# Vobla.net
KiCad netlist of a schematic drawn in Altium Designer
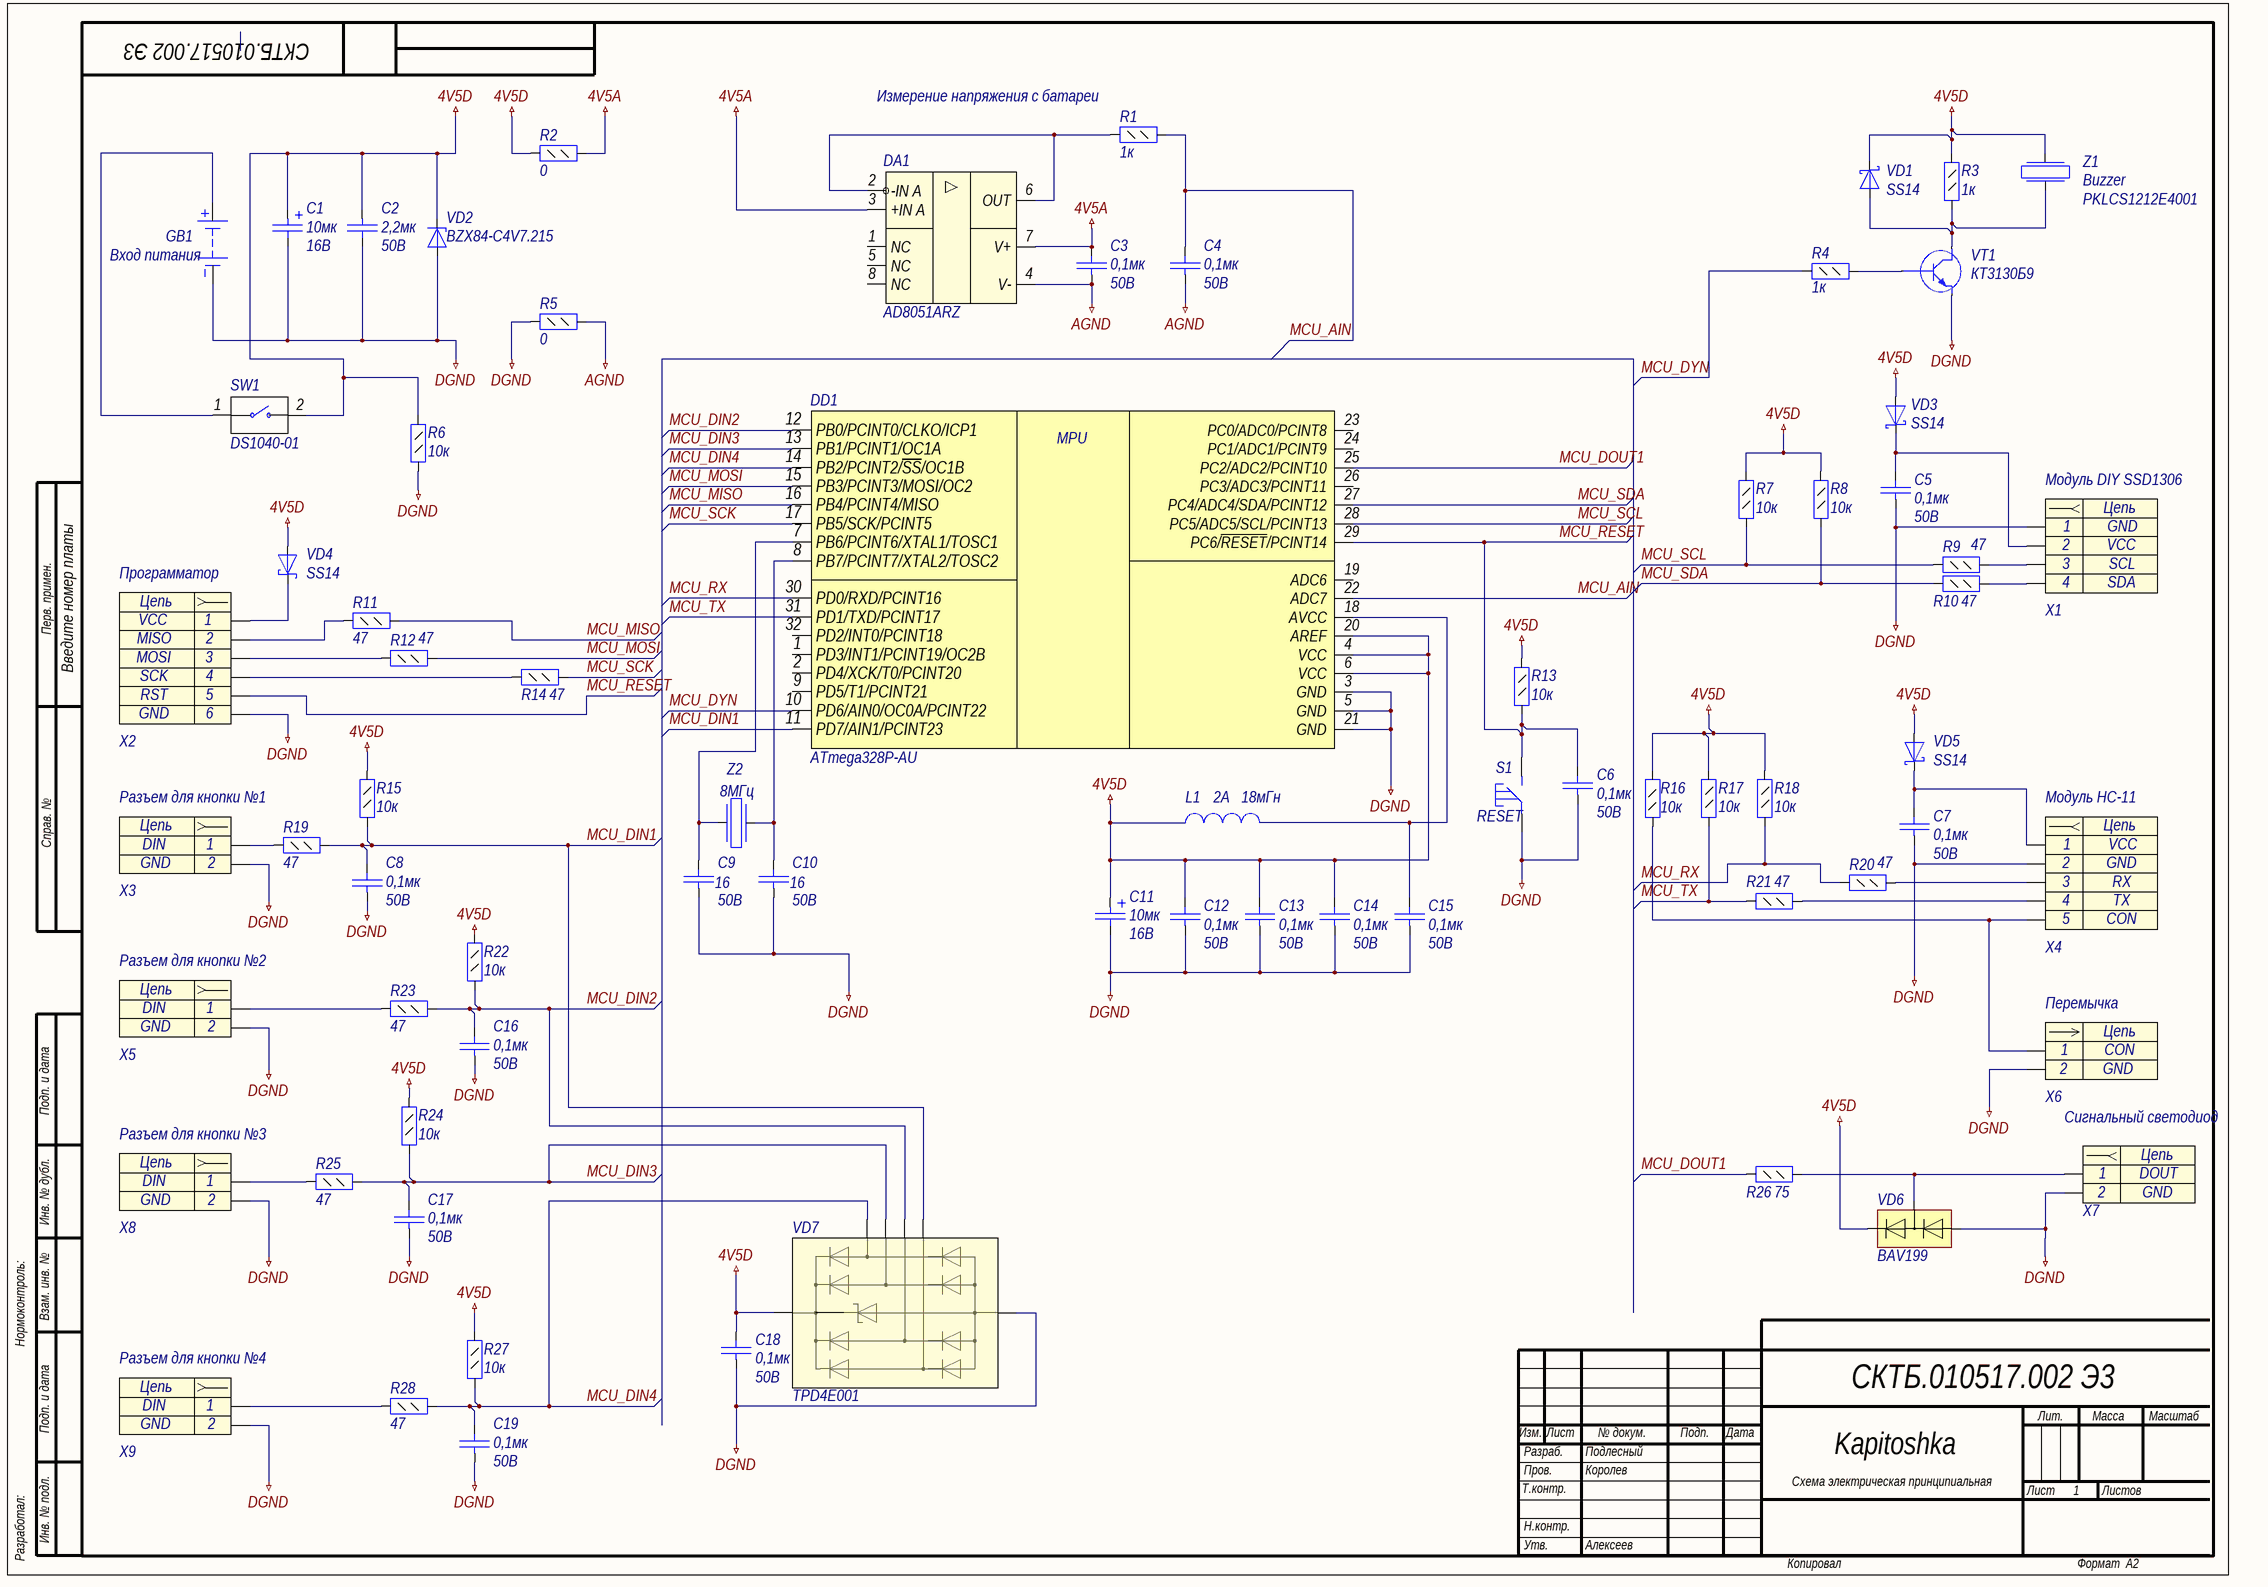
[diagram p0: Vobla.SchDoc]

(export (version "E")
  (design (tool "Eeschema 10.0.6"))
  (components
    (comp (ref "C1")
      (value "10мк")
      (footprint "Vobla:C1206")
      (description "Конденсатор полярный")
      (fields (field (name "VOLTAGE") "16В"))
      (libsource (lib "Vobla") (part "Capacitor_pol"))
    )
    (comp (ref "C2")
      (value "2,2мк")
      (footprint "Vobla:C0603")
      (description "Конденсатор")
      (fields (field (name "VOLTAGE") "50В"))
      (libsource (lib "Vobla") (part "Capacitor"))
    )
    (comp (ref "C3")
      (value "0,1мк")
      (footprint "Vobla:C0603")
      (description "Конденсатор")
      (fields (field (name "VOLTAGE") "50В"))
      (libsource (lib "Vobla") (part "Capacitor"))
    )
    (comp (ref "C4")
      (value "0,1мк")
      (footprint "Vobla:C0603")
      (description "Конденсатор")
      (fields (field (name "VOLTAGE") "50В"))
      (libsource (lib "Vobla") (part "Capacitor"))
    )
    (comp (ref "C5")
      (value "0,1мк")
      (footprint "Vobla:C0603")
      (description "Конденсатор")
      (fields (field (name "VOLTAGE") "50В"))
      (libsource (lib "Vobla") (part "Capacitor"))
    )
    (comp (ref "C6")
      (value "0,1мк")
      (footprint "Vobla:C0603")
      (description "Конденсатор")
      (fields (field (name "VOLTAGE") "50В"))
      (libsource (lib "Vobla") (part "Capacitor"))
    )
    (comp (ref "C7")
      (value "0,1мк")
      (footprint "Vobla:C0603")
      (description "Конденсатор")
      (fields (field (name "VOLTAGE") "50В"))
      (libsource (lib "Vobla") (part "Capacitor"))
    )
    (comp (ref "C8")
      (value "0,1мк")
      (footprint "Vobla:C0603")
      (description "Конденсатор")
      (fields (field (name "VOLTAGE") "50В"))
      (libsource (lib "Vobla") (part "Capacitor"))
    )
    (comp (ref "C9")
      (value "16")
      (footprint "Vobla:C0603")
      (description "Конденсатор")
      (fields (field (name "VOLTAGE") "50В"))
      (libsource (lib "Vobla") (part "Capacitor"))
    )
    (comp (ref "C10")
      (value "16")
      (footprint "Vobla:C0603")
      (description "Конденсатор")
      (fields (field (name "VOLTAGE") "50В"))
      (libsource (lib "Vobla") (part "Capacitor"))
    )
    (comp (ref "C11")
      (value "10мк")
      (footprint "Vobla:C1206")
      (description "Конденсатор полярный")
      (fields (field (name "VOLTAGE") "16В"))
      (libsource (lib "Vobla") (part "Capacitor_pol"))
    )
    (comp (ref "C12")
      (value "0,1мк")
      (footprint "Vobla:C0603")
      (description "Конденсатор")
      (fields (field (name "VOLTAGE") "50В"))
      (libsource (lib "Vobla") (part "Capacitor"))
    )
    (comp (ref "C13")
      (value "0,1мк")
      (footprint "Vobla:C0603")
      (description "Конденсатор")
      (fields (field (name "VOLTAGE") "50В"))
      (libsource (lib "Vobla") (part "Capacitor"))
    )
    (comp (ref "C14")
      (value "0,1мк")
      (footprint "Vobla:C0603")
      (description "Конденсатор")
      (fields (field (name "VOLTAGE") "50В"))
      (libsource (lib "Vobla") (part "Capacitor"))
    )
    (comp (ref "C15")
      (value "0,1мк")
      (footprint "Vobla:C0603")
      (description "Конденсатор")
      (fields (field (name "VOLTAGE") "50В"))
      (libsource (lib "Vobla") (part "Capacitor"))
    )
    (comp (ref "C16")
      (value "0,1мк")
      (footprint "Vobla:C0603")
      (description "Конденсатор")
      (fields (field (name "VOLTAGE") "50В"))
      (libsource (lib "Vobla") (part "Capacitor"))
    )
    (comp (ref "C17")
      (value "0,1мк")
      (footprint "Vobla:C0603")
      (description "Конденсатор")
      (fields (field (name "VOLTAGE") "50В"))
      (libsource (lib "Vobla") (part "Capacitor"))
    )
    (comp (ref "C18")
      (value "0,1мк")
      (footprint "Vobla:C0603")
      (description "Конденсатор")
      (fields (field (name "VOLTAGE") "50В"))
      (libsource (lib "Vobla") (part "Capacitor"))
    )
    (comp (ref "C19")
      (value "0,1мк")
      (footprint "Vobla:C0603")
      (description "Конденсатор")
      (fields (field (name "VOLTAGE") "50В"))
      (libsource (lib "Vobla") (part "Capacitor"))
    )
    (comp (ref "DA1")
      (value "AD8051ARZ")
      (footprint "Vobla:SO8_H")
      (description "ОУ")
      (fields (field (name "NAME") "AD8051ARZ"))
      (libsource (lib "Vobla") (part "AD8051ARZ"))
    )
    (comp (ref "DD1")
      (value "ATmega328P-AU")
      (footprint "Vobla:TQFP-32")
      (description "Микроконтроллер 64-pin")
      (fields (field (name "NAME") "ATmega328P-AU"))
      (libsource (lib "Vobla") (part "ATmega328P-AU"))
    )
    (comp (ref "GB1")
      (value "Вход питания")
      (footprint "Vobla:KLS5-818-С")
      (libsource (lib "Vobla") (part "Battery compartment"))
    )
    (comp (ref "L1")
      (value "18мГн")
      (footprint "Vobla:L0603_H")
      (description "Катушка индуктивности")
      (fields (field (name "IMAX") "2А"))
      (libsource (lib "Vobla") (part "Inductor"))
    )
    (comp (ref "R1")
      (value "1к")
      (footprint "Vobla:R0603")
      (description "Резистор")
      (libsource (lib "Vobla") (part "Resistor_0,125Вт"))
    )
    (comp (ref "R2")
      (value "0")
      (footprint "Vobla:R0603")
      (description "Резистор")
      (libsource (lib "Vobla") (part "Resistor_0,125Вт"))
    )
    (comp (ref "R3")
      (value "1к")
      (footprint "Vobla:R0603")
      (description "Резистор")
      (libsource (lib "") (part "Resistor_0,125Вт_1"))
    )
    (comp (ref "R4")
      (value "1к")
      (footprint "Vobla:R0603")
      (description "Резистор")
      (libsource (lib "Vobla") (part "Resistor_0,125Вт"))
    )
    (comp (ref "R5")
      (value "0")
      (footprint "Vobla:R0603")
      (description "Резистор")
      (libsource (lib "Vobla") (part "Resistor_0,125Вт"))
    )
    (comp (ref "R6")
      (value "10к")
      (footprint "Vobla:R0603")
      (description "Резистор")
      (libsource (lib "") (part "Resistor_0,125Вт_1"))
    )
    (comp (ref "R7")
      (value "10к")
      (footprint "Vobla:R0603")
      (description "Резистор")
      (libsource (lib "") (part "Resistor_0,125Вт_1"))
    )
    (comp (ref "R8")
      (value "10к")
      (footprint "Vobla:R0603")
      (description "Резистор")
      (libsource (lib "") (part "Resistor_0,125Вт_1"))
    )
    (comp (ref "R9")
      (value "47")
      (footprint "Vobla:R0603")
      (description "Резистор")
      (libsource (lib "Vobla") (part "Resistor_0,125Вт"))
    )
    (comp (ref "R10")
      (value "47")
      (footprint "Vobla:R0603")
      (description "Резистор")
      (libsource (lib "Vobla") (part "Resistor_0,125Вт"))
    )
    (comp (ref "R11")
      (value "47")
      (footprint "Vobla:R0603")
      (description "Резистор")
      (libsource (lib "Vobla") (part "Resistor_0,125Вт"))
    )
    (comp (ref "R12")
      (value "47")
      (footprint "Vobla:R0603")
      (description "Резистор")
      (libsource (lib "Vobla") (part "Resistor_0,125Вт"))
    )
    (comp (ref "R13")
      (value "10к")
      (footprint "Vobla:R0603")
      (description "Резистор")
      (libsource (lib "") (part "Resistor_0,125Вт_1"))
    )
    (comp (ref "R14")
      (value "47")
      (footprint "Vobla:R0603")
      (description "Резистор")
      (libsource (lib "Vobla") (part "Resistor_0,125Вт"))
    )
    (comp (ref "R15")
      (value "10к")
      (footprint "Vobla:R0603")
      (description "Резистор")
      (libsource (lib "") (part "Resistor_0,125Вт_1"))
    )
    (comp (ref "R16")
      (value "10к")
      (footprint "Vobla:R0603")
      (description "Резистор")
      (libsource (lib "") (part "Resistor_0,125Вт_2"))
    )
    (comp (ref "R17")
      (value "10к")
      (footprint "Vobla:R0603")
      (description "Резистор")
      (libsource (lib "") (part "Resistor_0,125Вт_1"))
    )
    (comp (ref "R18")
      (value "10к")
      (footprint "Vobla:R0603")
      (description "Резистор")
      (libsource (lib "") (part "Resistor_0,125Вт_1"))
    )
    (comp (ref "R19")
      (value "47")
      (footprint "Vobla:R0603")
      (description "Резистор")
      (libsource (lib "Vobla") (part "Resistor_0,125Вт"))
    )
    (comp (ref "R20")
      (value "47")
      (footprint "Vobla:R0603")
      (description "Резистор")
      (libsource (lib "Vobla") (part "Resistor_0,125Вт"))
    )
    (comp (ref "R21")
      (value "47")
      (footprint "Vobla:R0603")
      (description "Резистор")
      (libsource (lib "Vobla") (part "Resistor_0,125Вт"))
    )
    (comp (ref "R22")
      (value "10к")
      (footprint "Vobla:R0603")
      (description "Резистор")
      (libsource (lib "") (part "Resistor_0,125Вт_1"))
    )
    (comp (ref "R23")
      (value "47")
      (footprint "Vobla:R0603")
      (description "Резистор")
      (libsource (lib "Vobla") (part "Resistor_0,125Вт"))
    )
    (comp (ref "R24")
      (value "10к")
      (footprint "Vobla:R0603")
      (description "Резистор")
      (libsource (lib "") (part "Resistor_0,125Вт_1"))
    )
    (comp (ref "R25")
      (value "47")
      (footprint "Vobla:R0603")
      (description "Резистор")
      (libsource (lib "Vobla") (part "Resistor_0,125Вт"))
    )
    (comp (ref "R26")
      (value "75")
      (footprint "Vobla:R0603")
      (description "Резистор")
      (libsource (lib "Vobla") (part "Resistor_0,125Вт"))
    )
    (comp (ref "R27")
      (value "10к")
      (footprint "Vobla:R0603")
      (description "Резистор")
      (libsource (lib "") (part "Resistor_0,125Вт_1"))
    )
    (comp (ref "R28")
      (value "47")
      (footprint "Vobla:R0603")
      (description "Резистор")
      (libsource (lib "Vobla") (part "Resistor_0,125Вт"))
    )
    (comp (ref "S1")
      (value "RESET")
      (footprint "Vobla:DTSM 32")
      (description "Кнопка")
      (fields (field (name "NAME") "RESET"))
      (libsource (lib "Vobla") (part "Button_SMD"))
    )
    (comp (ref "SW1")
      (value "DS1040-01")
      (footprint "Vobla:DIP1")
      (description "DIP переключатель")
      (libsource (lib "Vobla") (part "DS1040-01"))
    )
    (comp (ref "VD1")
      (value "SS14")
      (footprint "Vobla:SMA")
      (description "Диод Шоттки")
      (libsource (lib "Vobla") (part "DiodeSchottky"))
    )
    (comp (ref "VD2")
      (value "BZX84-C4V7.215")
      (footprint "Vobla:SOT23-2_H")
      (description "Стабилитрон")
      (libsource (lib "Vobla") (part "DiodeZener"))
    )
    (comp (ref "VD3")
      (value "SS14")
      (footprint "Vobla:SMA")
      (description "Диод Шоттки")
      (libsource (lib "Vobla") (part "DiodeSchottky"))
    )
    (comp (ref "VD4")
      (value "SS14")
      (footprint "Vobla:SMA")
      (description "Диод Шоттки")
      (libsource (lib "Vobla") (part "DiodeSchottky"))
    )
    (comp (ref "VD5")
      (value "SS14")
      (footprint "Vobla:SMA")
      (description "Диод Шоттки")
      (libsource (lib "Vobla") (part "DiodeSchottky"))
    )
    (comp (ref "VD6")
      (value "BAV199")
      (footprint "Vobla:SOT23-3")
      (description "Диодная сборка")
      (libsource (lib "Vobla") (part "BAV199"))
    )
    (comp (ref "VD7")
      (value "TPD4E001")
      (footprint "Vobla:SOT23-6")
      (description "Диодная сборка")
      (fields (field (name "MANUFACTURER") "Texas Instruments"))
      (libsource (lib "Vobla") (part "TPD4E001"))
    )
    (comp (ref "VT1")
      (value "КТ3130Б9")
      (footprint "Vobla:SOT23-3")
      (fields (field (name "POWER") "0.1Вт"))
      (libsource (lib "Vobla") (part "КТ3130Б9"))
    )
    (comp (ref "X1")
      (value "Модуль DIY SSD1306")
      (footprint "Vobla:4HOLE_WIRE")
      (description "Разъем - 4 конт. розетка")
      (libsource (lib "Vobla") (part "Header_4_sct"))
    )
    (comp (ref "X2")
      (value "Программатор")
      (footprint "Vobla:6HOLE_WIRE")
      (description "Разъем - 5 конт. розетка")
      (libsource (lib "Vobla") (part "Header_6_sct"))
    )
    (comp (ref "X3")
      (value "Разъем для кнопки №1")
      (footprint "Vobla:2HOLE_Button")
      (description "Разъем - 2 конт. розетка")
      (libsource (lib "Vobla") (part "Header_2_sct"))
    )
    (comp (ref "X4")
      (value "Модуль HC-11")
      (footprint "Vobla:5HOLE_WIRE")
      (description "Разъем - 4 конт. розетка")
      (libsource (lib "Vobla") (part "Header_5_sct"))
    )
    (comp (ref "X5")
      (value "Разъем для кнопки №2")
      (footprint "Vobla:2HOLE_Button")
      (description "Разъем - 2 конт. розетка")
      (libsource (lib "Vobla") (part "Header_2_sct"))
    )
    (comp (ref "X6")
      (value "Перемычка")
      (footprint "Vobla:PLS2-2")
      (description "Разъем - 2 конт. вилка")
      (libsource (lib "Vobla") (part "Header_2_plg"))
    )
    (comp (ref "X7")
      (value "Сигнальный светодиод")
      (footprint "Vobla:2HOLE_Led")
      (description "Разъем - 2 конт. розетка")
      (libsource (lib "") (part "Header_2_sct_1"))
    )
    (comp (ref "X8")
      (value "Разъем для кнопки №3")
      (footprint "Vobla:2HOLE_Button")
      (description "Разъем - 2 конт. розетка")
      (libsource (lib "Vobla") (part "Header_2_sct"))
    )
    (comp (ref "X9")
      (value "Разъем для кнопки №4")
      (footprint "Vobla:2HOLE_Button")
      (description "Разъем - 2 конт. розетка")
      (libsource (lib "Vobla") (part "Header_2_sct"))
    )
    (comp (ref "Z1")
      (value "PKLCS1212E4001")
      (footprint "Vobla:Piezoelectric Sounder")
      (description "Пьезоизлучатель звуковой")
      (fields (field (name "ALTIUM_VALUE") "Buzzer"))
      (libsource (lib "Vobla") (part "Buzzer"))
    )
    (comp (ref "Z2")
      (value "8МГц")
      (footprint "Vobla:QSMD3.2x5")
      (description "Кварцевый резонатор")
      (libsource (lib "Vobla") (part "Crystal"))
    )
  )
  (nets
    (net (code "1") (name "/MCU_AIN") (class "Default")
      (node (ref "C4") (pin "2") (pinfunction "2_2") (pintype "passive"))
      (node (ref "DD1") (pin "22") (pinfunction "ADC7_22") (pintype "passive"))
      (node (ref "R1") (pin "2") (pinfunction "5_2") (pintype "passive"))
    )
    (net (code "2") (name "/MCU_DIN1") (class "Default")
      (node (ref "C8") (pin "2") (pinfunction "2_2") (pintype "passive"))
      (node (ref "DD1") (pin "11") (pinfunction "PD7/AIN1/PCINT23_11") (pintype "passive"))
      (node (ref "R15") (pin "2") (pinfunction "5_2") (pintype "passive"))
      (node (ref "R19") (pin "2") (pinfunction "5_2") (pintype "passive"))
      (node (ref "VD7") (pin "6") (pinfunction "IO4_6") (pintype "passive"))
    )
    (net (code "3") (name "/MCU_DIN2") (class "Default")
      (node (ref "C16") (pin "2") (pinfunction "2_2") (pintype "passive"))
      (node (ref "DD1") (pin "12") (pinfunction "PB0/PCINT0/CLKO/ICP1_12") (pintype "passive"))
      (node (ref "R22") (pin "2") (pinfunction "5_2") (pintype "passive"))
      (node (ref "R23") (pin "2") (pinfunction "5_2") (pintype "passive"))
      (node (ref "VD7") (pin "4") (pinfunction "IO3_4") (pintype "passive"))
    )
    (net (code "4") (name "/MCU_DIN3") (class "Default")
      (node (ref "C17") (pin "2") (pinfunction "2_2") (pintype "passive"))
      (node (ref "DD1") (pin "13") (pinfunction "PB1/PCINT1/OC1A_13") (pintype "passive"))
      (node (ref "R24") (pin "2") (pinfunction "5_2") (pintype "passive"))
      (node (ref "R25") (pin "2") (pinfunction "5_2") (pintype "passive"))
      (node (ref "VD7") (pin "3") (pinfunction "IO2_3") (pintype "passive"))
    )
    (net (code "5") (name "/MCU_DIN4") (class "Default")
      (node (ref "C19") (pin "2") (pinfunction "2_2") (pintype "passive"))
      (node (ref "DD1") (pin "14") (pinfunction "PB2/PCINT2/~{SS}/OC1B_14") (pintype "passive"))
      (node (ref "R27") (pin "2") (pinfunction "5_2") (pintype "passive"))
      (node (ref "R28") (pin "2") (pinfunction "5_2") (pintype "passive"))
      (node (ref "VD7") (pin "1") (pinfunction "IO1_1") (pintype "passive"))
    )
    (net (code "6") (name "/MCU_DOUT1") (class "Default")
      (node (ref "DD1") (pin "25") (pinfunction "PC2/ADC2/PCINT10_25") (pintype "passive"))
      (node (ref "R26") (pin "1") (pinfunction "1_1") (pintype "passive"))
    )
    (net (code "7") (name "/MCU_DYN") (class "Default")
      (node (ref "DD1") (pin "10") (pinfunction "PD6/AIN0/OC0A/PCINT22_10") (pintype "passive"))
      (node (ref "R4") (pin "1") (pinfunction "1_1") (pintype "passive"))
    )
    (net (code "8") (name "/MCU_MISO") (class "Default")
      (node (ref "DD1") (pin "16") (pinfunction "PB4/PCINT4/MISO_16") (pintype "passive"))
      (node (ref "R11") (pin "2") (pinfunction "5_2") (pintype "passive"))
    )
    (net (code "9") (name "/MCU_MOSI") (class "Default")
      (node (ref "DD1") (pin "15") (pinfunction "PB3/PCINT3/MOSI/OC2_15") (pintype "passive"))
      (node (ref "R12") (pin "2") (pinfunction "5_2") (pintype "passive"))
    )
    (net (code "10") (name "/MCU_RESET") (class "Default")
      (node (ref "C6") (pin "2") (pinfunction "2_2") (pintype "passive"))
      (node (ref "DD1") (pin "29") (pinfunction "PC6/~{RESET}/PCINT14_29") (pintype "passive"))
      (node (ref "R13") (pin "2") (pinfunction "5_2") (pintype "passive"))
      (node (ref "S1") (pin "3") (pinfunction "3_3") (pintype "passive"))
      (node (ref "X2") (pin "5") (pinfunction "5_5") (pintype "passive"))
    )
    (net (code "11") (name "/MCU_RX") (class "Default")
      (node (ref "DD1") (pin "30") (pinfunction "PD0/RXD/PCINT16_30") (pintype "passive"))
      (node (ref "R18") (pin "2") (pinfunction "5_2") (pintype "passive"))
      (node (ref "R20") (pin "1") (pinfunction "1_1") (pintype "passive"))
    )
    (net (code "12") (name "/MCU_SCK") (class "Default")
      (node (ref "DD1") (pin "17") (pinfunction "PB5/SCK/PCINT5_17") (pintype "passive"))
      (node (ref "R14") (pin "2") (pinfunction "5_2") (pintype "passive"))
    )
    (net (code "13") (name "/MCU_SCL") (class "Default")
      (node (ref "DD1") (pin "28") (pinfunction "PC5/ADC5/SCL/PCINT13_28") (pintype "passive"))
      (node (ref "R7") (pin "2") (pinfunction "5_2") (pintype "passive"))
      (node (ref "R9") (pin "1") (pinfunction "1_1") (pintype "passive"))
    )
    (net (code "14") (name "/MCU_SDA") (class "Default")
      (node (ref "DD1") (pin "27") (pinfunction "PC4/ADC4/SDA/PCINT12_27") (pintype "passive"))
      (node (ref "R10") (pin "1") (pinfunction "1_1") (pintype "passive"))
      (node (ref "R8") (pin "2") (pinfunction "5_2") (pintype "passive"))
    )
    (net (code "15") (name "/MCU_TX") (class "Default")
      (node (ref "DD1") (pin "31") (pinfunction "PD1/TXD/PCINT17_31") (pintype "passive"))
      (node (ref "R17") (pin "2") (pinfunction "5_2") (pintype "passive"))
      (node (ref "R21") (pin "1") (pinfunction "1_1") (pintype "passive"))
    )
    (net (code "16") (name "4V5A") (class "Default")
      (node (ref "C3") (pin "2") (pinfunction "2_2") (pintype "passive"))
      (node (ref "DA1") (pin "3") (pinfunction "+IN_A_3") (pintype "passive"))
      (node (ref "DA1") (pin "7") (pinfunction "V+_7") (pintype "passive"))
      (node (ref "R2") (pin "2") (pinfunction "5_2") (pintype "passive"))
    )
    (net (code "17") (name "4V5D") (class "Default")
      (node (ref "C1") (pin "1") (pinfunction "1_1") (pintype "passive"))
      (node (ref "C11") (pin "1") (pinfunction "1_1") (pintype "passive"))
      (node (ref "C12") (pin "2") (pinfunction "2_2") (pintype "passive"))
      (node (ref "C13") (pin "2") (pinfunction "2_2") (pintype "passive"))
      (node (ref "C14") (pin "2") (pinfunction "2_2") (pintype "passive"))
      (node (ref "C18") (pin "2") (pinfunction "2_2") (pintype "passive"))
      (node (ref "C2") (pin "1") (pinfunction "1_1") (pintype "passive"))
      (node (ref "DD1") (pin "20") (pinfunction "AREF_20") (pintype "passive"))
      (node (ref "DD1") (pin "4") (pinfunction "VCC_4") (pintype "passive"))
      (node (ref "DD1") (pin "6") (pinfunction "VCC_6") (pintype "passive"))
      (node (ref "L1") (pin "1") (pinfunction "1_1") (pintype "passive"))
      (node (ref "R13") (pin "1") (pinfunction "1_1") (pintype "passive"))
      (node (ref "R15") (pin "1") (pinfunction "1_1") (pintype "passive"))
      (node (ref "R16") (pin "2") (pinfunction "5_2") (pintype "passive"))
      (node (ref "R17") (pin "1") (pinfunction "1_1") (pintype "passive"))
      (node (ref "R18") (pin "1") (pinfunction "1_1") (pintype "passive"))
      (node (ref "R2") (pin "1") (pinfunction "1_1") (pintype "passive"))
      (node (ref "R22") (pin "1") (pinfunction "1_1") (pintype "passive"))
      (node (ref "R24") (pin "1") (pinfunction "1_1") (pintype "passive"))
      (node (ref "R27") (pin "1") (pinfunction "1_1") (pintype "passive"))
      (node (ref "R3") (pin "1") (pinfunction "1_1") (pintype "passive"))
      (node (ref "R6") (pin "1") (pinfunction "1_1") (pintype "passive"))
      (node (ref "R7") (pin "1") (pinfunction "1_1") (pintype "passive"))
      (node (ref "R8") (pin "1") (pinfunction "1_1") (pintype "passive"))
      (node (ref "SW1") (pin "2") (pintype "passive"))
      (node (ref "VD1") (pin "1") (pinfunction "K_1") (pintype "passive"))
      (node (ref "VD2") (pin "1") (pinfunction "K_1") (pintype "passive"))
      (node (ref "VD3") (pin "2") (pinfunction "A_2") (pintype "passive"))
      (node (ref "VD4") (pin "2") (pinfunction "A_2") (pintype "passive"))
      (node (ref "VD5") (pin "2") (pinfunction "A_2") (pintype "passive"))
      (node (ref "VD6") (pin "1") (pintype "passive"))
      (node (ref "VD7") (pin "5") (pinfunction "VCC_5") (pintype "passive"))
      (node (ref "Z1") (pin "2") (pinfunction "2_2") (pintype "passive"))
    )
    (net (code "18") (name "AGND") (class "Default")
      (node (ref "C3") (pin "1") (pinfunction "1_1") (pintype "passive"))
      (node (ref "C4") (pin "1") (pinfunction "1_1") (pintype "passive"))
      (node (ref "DA1") (pin "4") (pinfunction "V-_4") (pintype "passive"))
      (node (ref "R5") (pin "2") (pinfunction "5_2") (pintype "passive"))
    )
    (net (code "19") (name "DGND") (class "Default")
      (node (ref "C1") (pin "2") (pinfunction "2_2") (pintype "passive"))
      (node (ref "C10") (pin "1") (pinfunction "1_1") (pintype "passive"))
      (node (ref "C11") (pin "2") (pinfunction "2_2") (pintype "passive"))
      (node (ref "C12") (pin "1") (pinfunction "1_1") (pintype "passive"))
      (node (ref "C13") (pin "1") (pinfunction "1_1") (pintype "passive"))
      (node (ref "C14") (pin "1") (pinfunction "1_1") (pintype "passive"))
      (node (ref "C15") (pin "1") (pinfunction "1_1") (pintype "passive"))
      (node (ref "C16") (pin "1") (pinfunction "1_1") (pintype "passive"))
      (node (ref "C17") (pin "1") (pinfunction "1_1") (pintype "passive"))
      (node (ref "C18") (pin "1") (pinfunction "1_1") (pintype "passive"))
      (node (ref "C19") (pin "1") (pinfunction "1_1") (pintype "passive"))
      (node (ref "C2") (pin "2") (pinfunction "2_2") (pintype "passive"))
      (node (ref "C5") (pin "1") (pinfunction "1_1") (pintype "passive"))
      (node (ref "C6") (pin "1") (pinfunction "1_1") (pintype "passive"))
      (node (ref "C7") (pin "1") (pinfunction "1_1") (pintype "passive"))
      (node (ref "C8") (pin "1") (pinfunction "1_1") (pintype "passive"))
      (node (ref "C9") (pin "1") (pinfunction "1_1") (pintype "passive"))
      (node (ref "DD1") (pin "21") (pinfunction "GND_21") (pintype "passive"))
      (node (ref "DD1") (pin "3") (pinfunction "GND_3") (pintype "passive"))
      (node (ref "DD1") (pin "5") (pinfunction "GND_5") (pintype "passive"))
      (node (ref "GB1") (pin "2") (pinfunction "2_2") (pintype "passive"))
      (node (ref "R5") (pin "1") (pinfunction "1_1") (pintype "passive"))
      (node (ref "R6") (pin "2") (pinfunction "5_2") (pintype "passive"))
      (node (ref "S1") (pin "1") (pinfunction "1_1") (pintype "passive"))
      (node (ref "VD2") (pin "2") (pinfunction "A_2") (pintype "passive"))
      (node (ref "VD6") (pin "2") (pintype "passive"))
      (node (ref "VD7") (pin "2") (pinfunction "GND_2") (pintype "passive"))
      (node (ref "VT1") (pin "2") (pinfunction "Emitter_2") (pintype "passive"))
      (node (ref "X1") (pin "1") (pinfunction "1_1") (pintype "passive"))
      (node (ref "X2") (pin "6") (pinfunction "6_6") (pintype "passive"))
      (node (ref "X3") (pin "2") (pinfunction "2_2") (pintype "passive"))
      (node (ref "X4") (pin "2") (pinfunction "2_2") (pintype "passive"))
      (node (ref "X5") (pin "2") (pinfunction "2_2") (pintype "passive"))
      (node (ref "X6") (pin "2") (pinfunction "2_2") (pintype "passive"))
      (node (ref "X7") (pin "2") (pinfunction "2_2") (pintype "passive"))
      (node (ref "X8") (pin "2") (pinfunction "2_2") (pintype "passive"))
      (node (ref "X9") (pin "2") (pinfunction "2_2") (pintype "passive"))
    )
    (net (code "20") (name "Net-(DA1--IN_A)") (class "Default")
      (node (ref "DA1") (pin "2") (pinfunction "-IN_A_2") (pintype "passive"))
      (node (ref "DA1") (pin "6") (pinfunction "OUT_6") (pintype "passive"))
      (node (ref "R1") (pin "1") (pinfunction "1_1") (pintype "passive"))
    )
    (net (code "21") (name "Net-(DD1-AVCC)") (class "Default")
      (node (ref "C15") (pin "2") (pinfunction "2_2") (pintype "passive"))
      (node (ref "DD1") (pin "18") (pinfunction "AVCC_18") (pintype "passive"))
      (node (ref "L1") (pin "2") (pinfunction "2_2") (pintype "passive"))
    )
    (net (code "22") (name "Net-(DD1-PB6{slash}PCINT6{slash}XTAL1{slash}TOSC1)") (class "Default")
      (node (ref "C9") (pin "2") (pinfunction "2_2") (pintype "passive"))
      (node (ref "DD1") (pin "7") (pinfunction "PB6/PCINT6/XTAL1/TOSC1_7") (pintype "passive"))
      (node (ref "Z2") (pin "2") (pinfunction "2_2") (pintype "passive"))
    )
    (net (code "23") (name "Net-(DD1-PB7{slash}PCINT7{slash}XTAL2{slash}TOSC2)") (class "Default")
      (node (ref "C10") (pin "2") (pinfunction "2_2") (pintype "passive"))
      (node (ref "DD1") (pin "8") (pinfunction "PB7/PCINT7/XTAL2/TOSC2_8") (pintype "passive"))
      (node (ref "Z2") (pin "1") (pinfunction "1_1") (pintype "passive"))
    )
    (net (code "24") (name "Net-(GB1-Pad1)") (class "Default")
      (node (ref "GB1") (pin "1") (pinfunction "1_1") (pintype "passive"))
      (node (ref "SW1") (pin "1") (pintype "passive"))
    )
    (net (code "25") (name "Net-(R3-5)") (class "Default")
      (node (ref "R3") (pin "2") (pinfunction "5_2") (pintype "passive"))
      (node (ref "VD1") (pin "2") (pinfunction "A_2") (pintype "passive"))
      (node (ref "VT1") (pin "3") (pinfunction "Collector_3") (pintype "passive"))
      (node (ref "Z1") (pin "1") (pinfunction "1_1") (pintype "passive"))
    )
    (net (code "26") (name "Net-(R4-5)") (class "Default")
      (node (ref "R4") (pin "2") (pinfunction "5_2") (pintype "passive"))
      (node (ref "VT1") (pin "1") (pinfunction "Base_1") (pintype "passive"))
    )
    (net (code "27") (name "Net-(R9-5)") (class "Default")
      (node (ref "R9") (pin "2") (pinfunction "5_2") (pintype "passive"))
      (node (ref "X1") (pin "3") (pinfunction "3_3") (pintype "passive"))
    )
    (net (code "28") (name "Net-(R10-5)") (class "Default")
      (node (ref "R10") (pin "2") (pinfunction "5_2") (pintype "passive"))
      (node (ref "X1") (pin "4") (pinfunction "4_4") (pintype "passive"))
    )
    (net (code "29") (name "Net-(R11-Pad1)") (class "Default")
      (node (ref "R11") (pin "1") (pinfunction "1_1") (pintype "passive"))
      (node (ref "X2") (pin "2") (pinfunction "2_2") (pintype "passive"))
    )
    (net (code "30") (name "Net-(R12-Pad1)") (class "Default")
      (node (ref "R12") (pin "1") (pinfunction "1_1") (pintype "passive"))
      (node (ref "X2") (pin "3") (pinfunction "3_3") (pintype "passive"))
    )
    (net (code "31") (name "Net-(R14-Pad1)") (class "Default")
      (node (ref "R14") (pin "1") (pinfunction "1_1") (pintype "passive"))
      (node (ref "X2") (pin "4") (pinfunction "4_4") (pintype "passive"))
    )
    (net (code "32") (name "Net-(R16-Pad1)") (class "Default")
      (node (ref "R16") (pin "1") (pinfunction "1_1") (pintype "passive"))
      (node (ref "X4") (pin "5") (pinfunction "5_5") (pintype "passive"))
      (node (ref "X6") (pin "1") (pinfunction "1_1") (pintype "passive"))
    )
    (net (code "33") (name "Net-(R19-Pad1)") (class "Default")
      (node (ref "R19") (pin "1") (pinfunction "1_1") (pintype "passive"))
      (node (ref "X3") (pin "1") (pinfunction "1_1") (pintype "passive"))
    )
    (net (code "34") (name "Net-(R20-5)") (class "Default")
      (node (ref "R20") (pin "2") (pinfunction "5_2") (pintype "passive"))
      (node (ref "X4") (pin "3") (pinfunction "3_3") (pintype "passive"))
    )
    (net (code "35") (name "Net-(R21-5)") (class "Default")
      (node (ref "R21") (pin "2") (pinfunction "5_2") (pintype "passive"))
      (node (ref "X4") (pin "4") (pinfunction "4_4") (pintype "passive"))
    )
    (net (code "36") (name "Net-(R23-Pad1)") (class "Default")
      (node (ref "R23") (pin "1") (pinfunction "1_1") (pintype "passive"))
      (node (ref "X5") (pin "1") (pinfunction "1_1") (pintype "passive"))
    )
    (net (code "37") (name "Net-(R25-Pad1)") (class "Default")
      (node (ref "R25") (pin "1") (pinfunction "1_1") (pintype "passive"))
      (node (ref "X8") (pin "1") (pinfunction "1_1") (pintype "passive"))
    )
    (net (code "38") (name "Net-(R26-5)") (class "Default")
      (node (ref "R26") (pin "2") (pinfunction "5_2") (pintype "passive"))
      (node (ref "VD6") (pin "3") (pintype "passive"))
      (node (ref "X7") (pin "1") (pinfunction "1_1") (pintype "passive"))
    )
    (net (code "39") (name "Net-(R28-Pad1)") (class "Default")
      (node (ref "R28") (pin "1") (pinfunction "1_1") (pintype "passive"))
      (node (ref "X9") (pin "1") (pinfunction "1_1") (pintype "passive"))
    )
    (net (code "40") (name "Net-(VD3-K)") (class "Default")
      (node (ref "C5") (pin "2") (pinfunction "2_2") (pintype "passive"))
      (node (ref "VD3") (pin "1") (pinfunction "K_1") (pintype "passive"))
      (node (ref "X1") (pin "2") (pinfunction "2_2") (pintype "passive"))
    )
    (net (code "41") (name "Net-(VD4-K)") (class "Default")
      (node (ref "VD4") (pin "1") (pinfunction "K_1") (pintype "passive"))
      (node (ref "X2") (pin "1") (pinfunction "1_1") (pintype "passive"))
    )
    (net (code "42") (name "Net-(VD5-K)") (class "Default")
      (node (ref "C7") (pin "2") (pinfunction "2_2") (pintype "passive"))
      (node (ref "VD5") (pin "1") (pinfunction "K_1") (pintype "passive"))
      (node (ref "X4") (pin "1") (pinfunction "1_1") (pintype "passive"))
    )
    (net (code "43") (name "unconnected-(DA1-NC-Pad1)") (class "Default")
      (node (ref "DA1") (pin "1") (pinfunction "NC_1") (pintype "passive"))
    )
    (net (code "44") (name "unconnected-(DA1-NC-Pad5)") (class "Default")
      (node (ref "DA1") (pin "5") (pinfunction "NC_5") (pintype "passive"))
    )
    (net (code "45") (name "unconnected-(DA1-NC-Pad8)") (class "Default")
      (node (ref "DA1") (pin "8") (pinfunction "NC_8") (pintype "passive"))
    )
    (net (code "46") (name "unconnected-(DD1-ADC6-Pad19)") (class "Default")
      (node (ref "DD1") (pin "19") (pinfunction "ADC6_19") (pintype "passive"))
    )
    (net (code "47") (name "unconnected-(DD1-PC0{slash}ADC0{slash}PCINT8-Pad23)") (class "Default")
      (node (ref "DD1") (pin "23") (pinfunction "PC0/ADC0/PCINT8_23") (pintype "passive"))
    )
    (net (code "48") (name "unconnected-(DD1-PC1{slash}ADC1{slash}PCINT9-Pad24)") (class "Default")
      (node (ref "DD1") (pin "24") (pinfunction "PC1/ADC1/PCINT9_24") (pintype "passive"))
    )
    (net (code "49") (name "unconnected-(DD1-PC3{slash}ADC3{slash}PCINT11-Pad26)") (class "Default")
      (node (ref "DD1") (pin "26") (pinfunction "PC3/ADC3/PCINT11_26") (pintype "passive"))
    )
    (net (code "50") (name "unconnected-(DD1-PD2{slash}INT0{slash}PCINT18-Pad32)") (class "Default")
      (node (ref "DD1") (pin "32") (pinfunction "PD2/INT0/PCINT18_32") (pintype "passive"))
    )
    (net (code "51") (name "unconnected-(DD1-PD3{slash}INT1{slash}PCINT19{slash}OC2B-Pad1)") (class "Default")
      (node (ref "DD1") (pin "1") (pinfunction "PD3/INT1/PCINT19/OC2B_1") (pintype "passive"))
    )
    (net (code "52") (name "unconnected-(DD1-PD4{slash}XCK{slash}T0{slash}PCINT20-Pad2)") (class "Default")
      (node (ref "DD1") (pin "2") (pinfunction "PD4/XCK/T0/PCINT20_2") (pintype "passive"))
    )
    (net (code "53") (name "unconnected-(DD1-PD5{slash}T1{slash}PCINT21-Pad9)") (class "Default")
      (node (ref "DD1") (pin "9") (pinfunction "PD5/T1/PCINT21_9") (pintype "passive"))
    )
  )
)
